# OSO-BOOK-C1-01.net
KiCad netlist of a schematic drawn in EAGLE
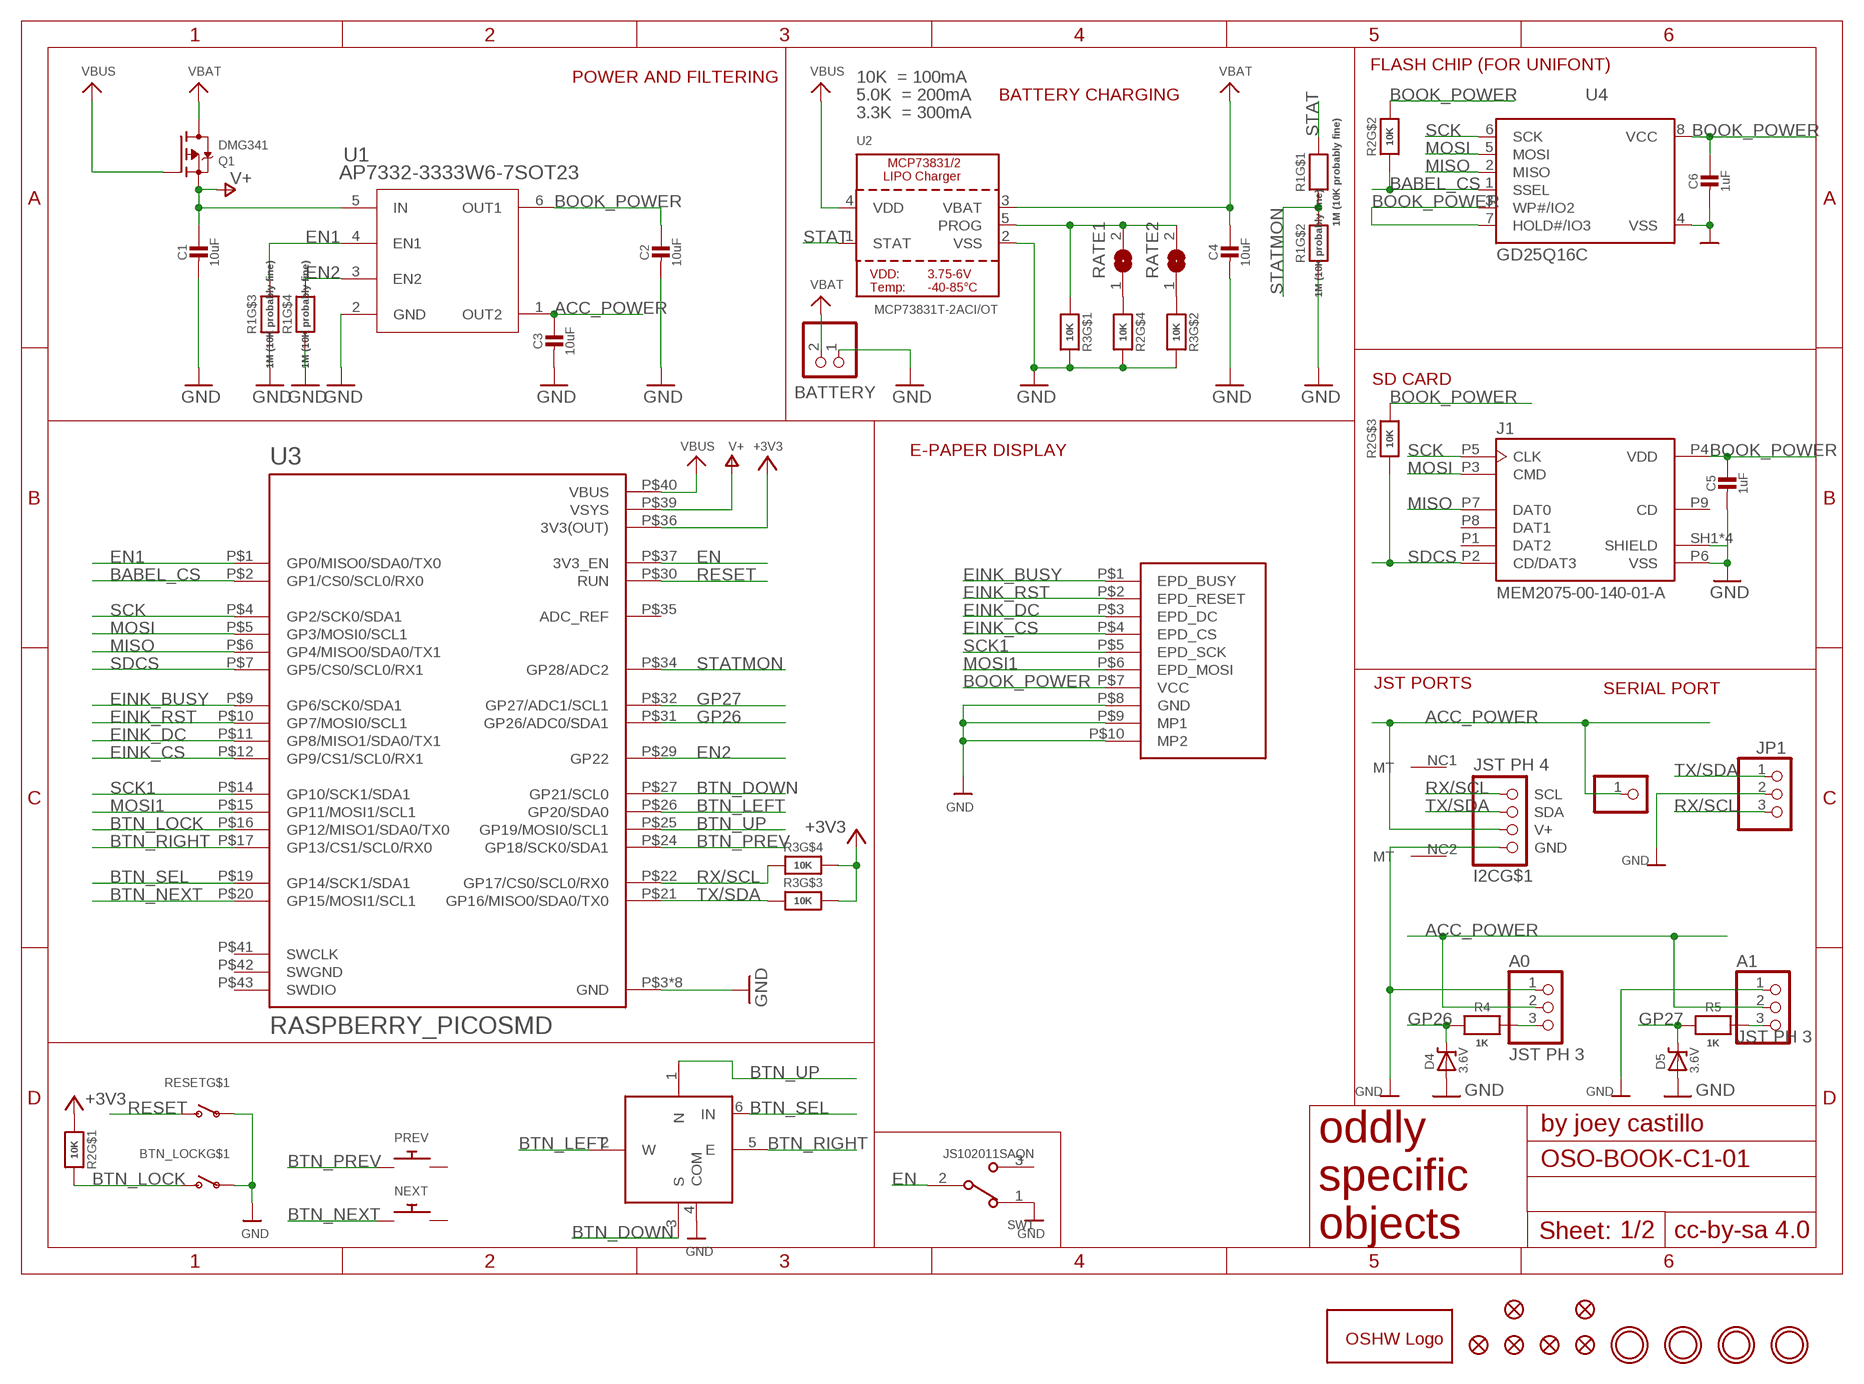
[diagram p0: schematic, sheet 1]
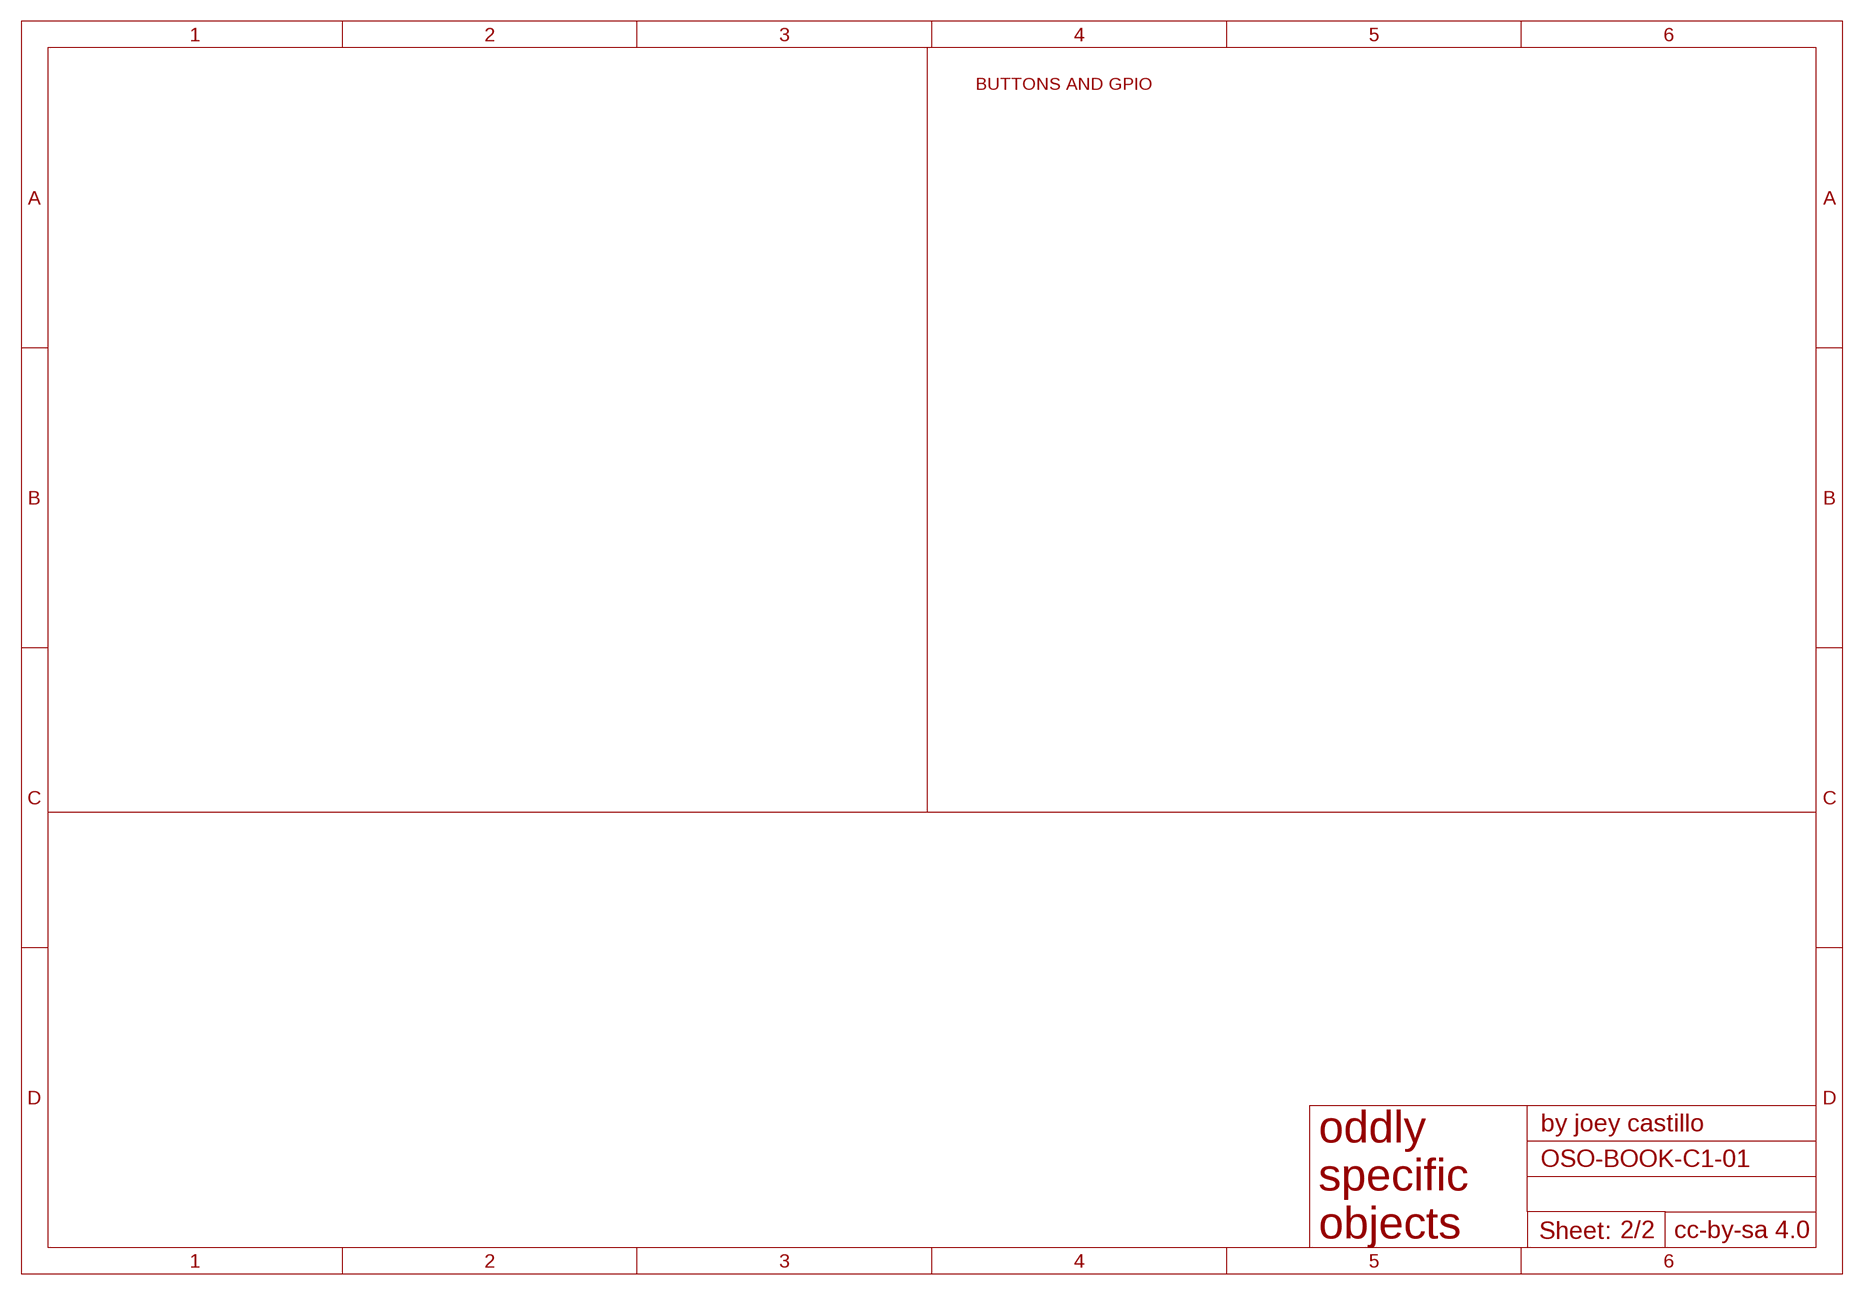
[diagram p1: schematic, sheet 2]

(export (version "E")
  (design (tool "Eeschema 10.0.6"))
  (components
    (comp (ref "A0")
      (value "JST PH 3")
      (footprint "eagle-import:JSTPH3")
      (libsource (lib "eagle-import") (part "CON_JST_PH_3PIN"))
    )
    (comp (ref "A1")
      (value "JST PH 3")
      (footprint "eagle-import:JSTPH3")
      (libsource (lib "eagle-import") (part "CON_JST_PH_3PIN"))
    )
    (comp (ref "BATTERY")
      (value "JSTPH")
      (footprint "eagle-import:JSTPH2")
      (libsource (lib "eagle-import") (part "CON_JST_PH_2PIN"))
    )
    (comp (ref "BTN_LOCK")
      (value "SWITCH_SPSTTL3330A")
      (footprint "eagle-import:TL3330A")
      (libsource (lib "eagle-import") (part "SWITCH_SPSTTL3330A"))
    )
    (comp (ref "C1")
      (value "10uF")
      (footprint "eagle-import:0805-NO")
      (libsource (lib "eagle-import") (part "CAP_CERAMIC0805-NOOUTLINE"))
    )
    (comp (ref "C2")
      (value "10uF")
      (footprint "eagle-import:0805-NO")
      (libsource (lib "eagle-import") (part "CAP_CERAMIC0805-NOOUTLINE"))
    )
    (comp (ref "C3")
      (value "10uF")
      (footprint "eagle-import:0805-NO")
      (libsource (lib "eagle-import") (part "CAP_CERAMIC0805-NOOUTLINE"))
    )
    (comp (ref "C4")
      (value "10uF")
      (footprint "eagle-import:0805-NO")
      (libsource (lib "eagle-import") (part "CAP_CERAMIC0805-NOOUTLINE"))
    )
    (comp (ref "C5")
      (value "1uF")
      (footprint "eagle-import:0805-NO")
      (libsource (lib "eagle-import") (part "CAP_CERAMIC0805-NOOUTLINE"))
    )
    (comp (ref "C6")
      (value "1uF")
      (footprint "eagle-import:0805-NO")
      (libsource (lib "eagle-import") (part "CAP_CERAMIC0805-NOOUTLINE"))
    )
    (comp (ref "D4")
      (value "3.6V")
      (footprint "eagle-import:SOD-123")
      (libsource (lib "eagle-import") (part "DIODE-ZENERSOD123"))
    )
    (comp (ref "D5")
      (value "3.6V")
      (footprint "eagle-import:SOD-123")
      (libsource (lib "eagle-import") (part "DIODE-ZENERSOD123"))
    )
    (comp (ref "FID1")
      (value "FIDUCIAL_1MM")
      (footprint "eagle-import:FIDUCIAL_1MM")
      (libsource (lib "eagle-import") (part "FIDUCIAL_1MM"))
    )
    (comp (ref "FID2")
      (value "FIDUCIAL_1MM")
      (footprint "eagle-import:FIDUCIAL_1MM")
      (libsource (lib "eagle-import") (part "FIDUCIAL_1MM"))
    )
    (comp (ref "FID3")
      (value "FIDUCIAL_1MM")
      (footprint "eagle-import:FIDUCIAL_1MM")
      (libsource (lib "eagle-import") (part "FIDUCIAL_1MM"))
    )
    (comp (ref "FID4")
      (value "FIDUCIAL_1MM")
      (footprint "eagle-import:FIDUCIAL_1MM")
      (libsource (lib "eagle-import") (part "FIDUCIAL_1MM"))
    )
    (comp (ref "FID5")
      (value "FIDUCIAL_1MM")
      (footprint "eagle-import:FIDUCIAL_1MM")
      (libsource (lib "eagle-import") (part "FIDUCIAL_1MM"))
    )
    (comp (ref "FID6")
      (value "FIDUCIAL_1MM")
      (footprint "eagle-import:FIDUCIAL_1MM")
      (libsource (lib "eagle-import") (part "FIDUCIAL_1MM"))
    )
    (comp (ref "GOLD_ORB_SM1")
      (value "OSHWLOGOLOGO5MM")
      (footprint "eagle-import:OSHW_5MM")
      (libsource (lib "eagle-import") (part "OSHWLOGOLOGO5MM"))
    )
    (comp (ref "I2C")
      (value "JST PH 4")
      (footprint "eagle-import:JSTPH4")
      (libsource (lib "eagle-import") (part "STEMMA_I2C_RASMT"))
    )
    (comp (ref "J1")
      (value "MEM2075-00-140-01-A")
      (footprint "eagle-import:GCT_MEM2075-00-140-01-A")
      (fields (field (name "MF") "Global Connector Technology"))
      (libsource (lib "eagle-import") (part "MEM2075-00-140-01-A"))
    )
    (comp (ref "JP1")
      (value "PINHD-1X3")
      (footprint "eagle-import:1X03")
      (libsource (lib "eagle-import") (part "PINHD-1X3"))
    )
    (comp (ref "JP2")
      (value "PINHD-1X1")
      (footprint "eagle-import:1X01")
      (libsource (lib "eagle-import") (part "PINHD-1X1"))
    )
    (comp (ref "NEXT")
      (value "SWITCH_PUSHBUTTON_3.5X6MM")
      (footprint "eagle-import:TACTILE_3X6MM")
      (libsource (lib "eagle-import") (part "SWITCH_PUSHBUTTON_3.5X6MM"))
    )
    (comp (ref "PREV")
      (value "SWITCH_PUSHBUTTON_3.5X6MM")
      (footprint "eagle-import:TACTILE_3X6MM")
      (libsource (lib "eagle-import") (part "SWITCH_PUSHBUTTON_3.5X6MM"))
    )
    (comp (ref "Q1")
      (value "DMG341")
      (footprint "eagle-import:SOT23-R")
      (libsource (lib "eagle-import") (part "MOSFET-P"))
    )
    (comp (ref "R1")
      (value "1M (10K probably fine)")
      (footprint "eagle-import:EXBV8V")
      (fields (field (name "MANUFACTURER_PART_NUMBER") "EXBV8V103JV"))
      (libsource (lib "eagle-import") (part "EXB-V8V103JV-GOOD"))
    )
    (comp (ref "R2")
      (value "10K")
      (footprint "eagle-import:EXBV8V")
      (fields (field (name "MANUFACTURER_PART_NUMBER") "EXBV8V103JV"))
      (libsource (lib "eagle-import") (part "EXB-V8V103JV-GOOD"))
    )
    (comp (ref "R3")
      (value "10K")
      (footprint "eagle-import:EXBV8V")
      (fields (field (name "MANUFACTURER_PART_NUMBER") "EXBV8V103JV"))
      (libsource (lib "eagle-import") (part "EXB-V8V103JV-GOOD"))
    )
    (comp (ref "R4")
      (value "1K")
      (footprint "eagle-import:0805-NO")
      (libsource (lib "eagle-import") (part "RESISTOR0805_NOOUTLINE"))
    )
    (comp (ref "R5")
      (value "1K")
      (footprint "eagle-import:0805-NO")
      (libsource (lib "eagle-import") (part "RESISTOR0805_NOOUTLINE"))
    )
    (comp (ref "RATE1")
      (value "SOLDERJUMPER")
      (footprint "eagle-import:SOLDERJUMPER_ARROW_NOPASTE")
      (libsource (lib "eagle-import") (part "SOLDERJUMPER"))
    )
    (comp (ref "RATE2")
      (value "SOLDERJUMPER")
      (footprint "eagle-import:SOLDERJUMPER_ARROW_NOPASTE")
      (libsource (lib "eagle-import") (part "SOLDERJUMPER"))
    )
    (comp (ref "RESET")
      (value "SWITCH_SPSTTL3330A")
      (footprint "eagle-import:TL3330A")
      (libsource (lib "eagle-import") (part "SWITCH_SPSTTL3330A"))
    )
    (comp (ref "SW1")
      (value "JS102011SAQN")
      (footprint "eagle-import:SW_JS102011SAQN")
      (fields (field (name "DIGI-KEY_PART_NUMBER") "401-1999-1-ND") (field (name "MF") "C&K"))
      (libsource (lib "eagle-import") (part "JS102011SAQN"))
    )
    (comp (ref "SW2")
      (value "NAVSWITCHSKQUABAUE010")
      (footprint "eagle-import:SKQUBAE010")
      (libsource (lib "eagle-import") (part "NAVSWITCHSKQUABAUE010"))
    )
    (comp (ref "U$1")
      (value "MOUNTINGHOLE2.5")
      (footprint "eagle-import:MOUNTINGHOLE_2.5_PLATED")
      (libsource (lib "eagle-import") (part "MOUNTINGHOLE2.5"))
    )
    (comp (ref "U$4")
      (value "MOUNTINGHOLE2.5")
      (footprint "eagle-import:MOUNTINGHOLE_2.5_PLATED")
      (libsource (lib "eagle-import") (part "MOUNTINGHOLE2.5"))
    )
    (comp (ref "U$5")
      (value "MOUNTINGHOLE2.5")
      (footprint "eagle-import:MOUNTINGHOLE_2.5_PLATED")
      (libsource (lib "eagle-import") (part "MOUNTINGHOLE2.5"))
    )
    (comp (ref "U$7")
      (value "MOUNTINGHOLE2.5")
      (footprint "eagle-import:MOUNTINGHOLE_2.5_PLATED")
      (libsource (lib "eagle-import") (part "MOUNTINGHOLE2.5"))
    )
    (comp (ref "U$11")
      (value "OSO-BOOK-C2-01")
      (footprint "eagle-import:OSO-BOOK-C2-01")
      (libsource (lib "eagle-import") (part "OSO-BOOK-C2-01"))
    )
    (comp (ref "U1")
      (value "AP7332-3333W6-7SOT23")
      (footprint "eagle-import:SOT23-6")
      (libsource (lib "eagle-import") (part "AP7332-3333W6-7SOT23"))
    )
    (comp (ref "U2")
      (value "MCP73831T-2ACI/OT")
      (footprint "eagle-import:SOT23-5")
      (libsource (lib "eagle-import") (part "MCP73831/2"))
    )
    (comp (ref "U3")
      (value "RASPBERRY_PICOSMD")
      (footprint "eagle-import:PICO-PKG-SMD")
      (libsource (lib "eagle-import") (part "RASPBERRY_PICOSMD"))
    )
    (comp (ref "U4")
      (value "GD25Q16C")
      (footprint "eagle-import:MICROBUILDER_SOIC8_150MIL")
      (libsource (lib "eagle-import") (part "MICROBUILDER_SPIFLASH_SOIC8"))
    )
  )
  (nets
    (net (code "1") (name "+3V3") (class "Default")
      (node (ref "R2") (pin "1") (pinfunction "1_1") (pintype "passive"))
      (node (ref "R3") (pin "5") (pinfunction "2_5") (pintype "passive"))
      (node (ref "R3") (pin "6") (pinfunction "2_6") (pintype "passive"))
      (node (ref "U3") (pin "P$36") (pinfunction "3V3(OUT)_P$36") (pintype "power_in"))
    )
    (net (code "2") (name "ACC_POWER") (class "Default")
      (node (ref "A0") (pin "2") (pinfunction "2_2") (pintype "passive"))
      (node (ref "A1") (pin "2") (pinfunction "2_2") (pintype "passive"))
      (node (ref "C3") (pin "1") (pinfunction "1_1") (pintype "passive"))
      (node (ref "I2C") (pin "2") (pinfunction "V+_2") (pintype "passive"))
      (node (ref "JP2") (pin "1") (pinfunction "1_1") (pintype "passive"))
      (node (ref "U1") (pin "1") (pinfunction "OUT2_1") (pintype "output"))
    )
    (net (code "3") (name "BABEL_CS") (class "Default")
      (node (ref "R2") (pin "2") (pinfunction "1_2") (pintype "passive"))
      (node (ref "U3") (pin "P$2") (pinfunction "GP1/CS0/SCL0/RX0_P$2") (pintype "bidirectional"))
      (node (ref "U4") (pin "1") (pinfunction "SSEL_1") (pintype "bidirectional"))
    )
    (net (code "4") (name "BOOK_POWER") (class "Default")
      (node (ref "C2") (pin "1") (pinfunction "1_1") (pintype "passive"))
      (node (ref "C5") (pin "1") (pinfunction "1_1") (pintype "passive"))
      (node (ref "C6") (pin "1") (pinfunction "1_1") (pintype "passive"))
      (node (ref "J1") (pin "P4") (pinfunction "VDD_P4") (pintype "power_in"))
      (node (ref "R2") (pin "6") (pinfunction "2_6") (pintype "passive"))
      (node (ref "R2") (pin "7") (pinfunction "2_7") (pintype "passive"))
      (node (ref "U$11") (pin "P$7") (pinfunction "VCC_P$7") (pintype "bidirectional"))
      (node (ref "U1") (pin "6") (pinfunction "OUT1_6") (pintype "output"))
      (node (ref "U4") (pin "3") (pinfunction "WP#/IO2_3") (pintype "bidirectional"))
      (node (ref "U4") (pin "7") (pinfunction "HOLD#/IO3_7") (pintype "bidirectional"))
      (node (ref "U4") (pin "8") (pinfunction "VCC_8") (pintype "bidirectional"))
    )
    (net (code "5") (name "BTN_DOWN") (class "Default")
      (node (ref "SW2") (pin "3") (pinfunction "S_3") (pintype "bidirectional"))
      (node (ref "U3") (pin "P$27") (pinfunction "GP21/SCL0_P$27") (pintype "bidirectional"))
    )
    (net (code "6") (name "BTN_LEFT") (class "Default")
      (node (ref "SW2") (pin "2") (pinfunction "W_2") (pintype "bidirectional"))
      (node (ref "U3") (pin "P$26") (pinfunction "GP20/SDA0_P$26") (pintype "bidirectional"))
    )
    (net (code "7") (name "BTN_LOCK") (class "Default")
      (node (ref "BTN_LOCK") (pin "P$2") (pinfunction "S_P$2") (pintype "passive"))
      (node (ref "R2") (pin "8") (pinfunction "2_8") (pintype "passive"))
      (node (ref "U3") (pin "P$16") (pinfunction "GP12/MISO1/SDA0/TX0_P$16") (pintype "bidirectional"))
    )
    (net (code "8") (name "BTN_NEXT") (class "Default")
      (node (ref "NEXT") (pin "P$1") (pinfunction "P$1_P$1") (pintype "passive"))
      (node (ref "U3") (pin "P$20") (pinfunction "GP15/MOSI1/SCL1_P$20") (pintype "bidirectional"))
    )
    (net (code "9") (name "BTN_PREV") (class "Default")
      (node (ref "PREV") (pin "P$1") (pinfunction "P$1_P$1") (pintype "passive"))
      (node (ref "U3") (pin "P$24") (pinfunction "GP18/SCK0/SDA1_P$24") (pintype "bidirectional"))
    )
    (net (code "10") (name "BTN_RIGHT") (class "Default")
      (node (ref "SW2") (pin "5") (pinfunction "E_5") (pintype "bidirectional"))
      (node (ref "U3") (pin "P$17") (pinfunction "GP13/CS1/SCL0/RX0_P$17") (pintype "bidirectional"))
    )
    (net (code "11") (name "BTN_SEL") (class "Default")
      (node (ref "SW2") (pin "6") (pinfunction "IN_6") (pintype "bidirectional"))
      (node (ref "U3") (pin "P$19") (pinfunction "GP14/SCK1/SDA1_P$19") (pintype "bidirectional"))
    )
    (net (code "12") (name "BTN_UP") (class "Default")
      (node (ref "SW2") (pin "1") (pinfunction "N_1") (pintype "bidirectional"))
      (node (ref "U3") (pin "P$25") (pinfunction "GP19/MOSI0/SCL1_P$25") (pintype "bidirectional"))
    )
    (net (code "13") (name "EINK_BUSY") (class "Default")
      (node (ref "U$11") (pin "P$1") (pinfunction "EPD_BUSY_P$1") (pintype "bidirectional"))
      (node (ref "U3") (pin "P$9") (pinfunction "GP6/SCK0/SDA1_P$9") (pintype "bidirectional"))
    )
    (net (code "14") (name "EINK_CS") (class "Default")
      (node (ref "U$11") (pin "P$4") (pinfunction "EPD_CS_P$4") (pintype "bidirectional"))
      (node (ref "U3") (pin "P$12") (pinfunction "GP9/CS1/SCL0/RX1_P$12") (pintype "bidirectional"))
    )
    (net (code "15") (name "EINK_DC") (class "Default")
      (node (ref "U$11") (pin "P$3") (pinfunction "EPD_DC_P$3") (pintype "bidirectional"))
      (node (ref "U3") (pin "P$11") (pinfunction "GP8/MISO1/SDA0/TX1_P$11") (pintype "bidirectional"))
    )
    (net (code "16") (name "EINK_RST") (class "Default")
      (node (ref "U$11") (pin "P$2") (pinfunction "EPD_RESET_P$2") (pintype "bidirectional"))
      (node (ref "U3") (pin "P$10") (pinfunction "GP7/MOSI0/SCL1_P$10") (pintype "bidirectional"))
    )
    (net (code "17") (name "EN") (class "Default")
      (node (ref "SW1") (pin "2") (pinfunction "2_2") (pintype "passive"))
      (node (ref "U3") (pin "P$37") (pinfunction "3V3_EN_P$37") (pintype "input"))
    )
    (net (code "18") (name "EN1") (class "Default")
      (node (ref "R1") (pin "3") (pinfunction "1_3") (pintype "passive"))
      (node (ref "U1") (pin "4") (pinfunction "EN1_4") (pintype "input"))
      (node (ref "U3") (pin "P$1") (pinfunction "GP0/MISO0/SDA0/TX0_P$1") (pintype "bidirectional"))
    )
    (net (code "19") (name "EN2") (class "Default")
      (node (ref "R1") (pin "4") (pinfunction "1_4") (pintype "passive"))
      (node (ref "U1") (pin "3") (pinfunction "EN2_3") (pintype "input"))
      (node (ref "U3") (pin "P$29") (pinfunction "GP22_P$29") (pintype "bidirectional"))
    )
    (net (code "20") (name "GND") (class "Default")
      (node (ref "A0") (pin "1") (pinfunction "1_1") (pintype "passive"))
      (node (ref "A1") (pin "1") (pinfunction "1_1") (pintype "passive"))
      (node (ref "BATTERY") (pin "1") (pinfunction "1_1") (pintype "passive"))
      (node (ref "BTN_LOCK") (pin "P$1") (pinfunction "P_P$1") (pintype "passive"))
      (node (ref "C1") (pin "2") (pinfunction "2_2") (pintype "passive"))
      (node (ref "C2") (pin "2") (pinfunction "2_2") (pintype "passive"))
      (node (ref "C3") (pin "2") (pinfunction "2_2") (pintype "passive"))
      (node (ref "C4") (pin "2") (pinfunction "2_2") (pintype "passive"))
      (node (ref "C5") (pin "2") (pinfunction "2_2") (pintype "passive"))
      (node (ref "C6") (pin "2") (pinfunction "2_2") (pintype "passive"))
      (node (ref "D4") (pin "A") (pinfunction "A_A") (pintype "passive"))
      (node (ref "D5") (pin "A") (pinfunction "A_A") (pintype "passive"))
      (node (ref "I2C") (pin "1") (pinfunction "GND_1") (pintype "passive"))
      (node (ref "J1") (pin "P6") (pinfunction "VSS_P6") (pintype "power_in"))
      (node (ref "J1") (pin "SH1") (pinfunction "SHIELD_SH1") (pintype "power_in"))
      (node (ref "J1") (pin "SH2") (pinfunction "SHIELD_SH2") (pintype "power_in"))
      (node (ref "J1") (pin "SH3") (pinfunction "SHIELD_SH3") (pintype "power_in"))
      (node (ref "J1") (pin "SH4") (pinfunction "SHIELD_SH4") (pintype "power_in"))
      (node (ref "JP1") (pin "2") (pinfunction "2_2") (pintype "passive"))
      (node (ref "R1") (pin "2") (pinfunction "1_2") (pintype "passive"))
      (node (ref "R1") (pin "5") (pinfunction "2_5") (pintype "passive"))
      (node (ref "R1") (pin "6") (pinfunction "2_6") (pintype "passive"))
      (node (ref "R2") (pin "5") (pinfunction "2_5") (pintype "passive"))
      (node (ref "R3") (pin "7") (pinfunction "2_7") (pintype "passive"))
      (node (ref "R3") (pin "8") (pinfunction "2_8") (pintype "passive"))
      (node (ref "RESET") (pin "P$1") (pinfunction "P_P$1") (pintype "passive"))
      (node (ref "SW1") (pin "1") (pinfunction "1_1") (pintype "passive"))
      (node (ref "SW2") (pin "4") (pinfunction "COM_4") (pintype "bidirectional"))
      (node (ref "U$11") (pin "P$10") (pinfunction "MP2_P$10") (pintype "bidirectional"))
      (node (ref "U$11") (pin "P$8") (pinfunction "GND_P$8") (pintype "bidirectional"))
      (node (ref "U$11") (pin "P$9") (pinfunction "MP1_P$9") (pintype "bidirectional"))
      (node (ref "U1") (pin "2") (pinfunction "GND_2") (pintype "power_in"))
      (node (ref "U2") (pin "2") (pinfunction "VSS_2") (pintype "power_in"))
      (node (ref "U3") (pin "P$13") (pinfunction "GND_P$13") (pintype "power_in"))
      (node (ref "U3") (pin "P$18") (pinfunction "GND_P$18") (pintype "power_in"))
      (node (ref "U3") (pin "P$23") (pinfunction "GND_P$23") (pintype "power_in"))
      (node (ref "U3") (pin "P$28") (pinfunction "GND_P$28") (pintype "power_in"))
      (node (ref "U3") (pin "P$3") (pinfunction "GND_P$3") (pintype "power_in"))
      (node (ref "U3") (pin "P$33") (pinfunction "GND_P$33") (pintype "power_in"))
      (node (ref "U3") (pin "P$38") (pinfunction "GND_P$38") (pintype "power_in"))
      (node (ref "U3") (pin "P$8") (pinfunction "GND_P$8") (pintype "power_in"))
      (node (ref "U4") (pin "4") (pinfunction "VSS_4") (pintype "bidirectional"))
    )
    (net (code "21") (name "GP26") (class "Default")
      (node (ref "D4") (pin "C") (pinfunction "C_C") (pintype "passive"))
      (node (ref "R4") (pin "2") (pinfunction "2_2") (pintype "passive"))
      (node (ref "U3") (pin "P$31") (pinfunction "GP26/ADC0/SDA1_P$31") (pintype "bidirectional"))
    )
    (net (code "22") (name "GP27") (class "Default")
      (node (ref "D5") (pin "C") (pinfunction "C_C") (pintype "passive"))
      (node (ref "R5") (pin "2") (pinfunction "2_2") (pintype "passive"))
      (node (ref "U3") (pin "P$32") (pinfunction "GP27/ADC1/SCL1_P$32") (pintype "bidirectional"))
    )
    (net (code "23") (name "MISO") (class "Default")
      (node (ref "J1") (pin "P7") (pinfunction "DAT0_P7") (pintype "bidirectional"))
      (node (ref "U3") (pin "P$6") (pinfunction "GP4/MISO0/SDA0/TX1_P$6") (pintype "bidirectional"))
      (node (ref "U4") (pin "2") (pinfunction "MISO_2") (pintype "bidirectional"))
    )
    (net (code "24") (name "MOSI") (class "Default")
      (node (ref "J1") (pin "P3") (pinfunction "CMD_P3") (pintype "bidirectional"))
      (node (ref "U3") (pin "P$5") (pinfunction "GP3/MOSI0/SCL1_P$5") (pintype "bidirectional"))
      (node (ref "U4") (pin "5") (pinfunction "MOSI_5") (pintype "bidirectional"))
    )
    (net (code "25") (name "MOSI1") (class "Default")
      (node (ref "U$11") (pin "P$6") (pinfunction "EPD_MOSI_P$6") (pintype "bidirectional"))
      (node (ref "U3") (pin "P$15") (pinfunction "GP11/MOSI1/SCL1_P$15") (pintype "bidirectional"))
    )
    (net (code "26") (name "Net-(A0-Pad3)") (class "Default")
      (node (ref "A0") (pin "3") (pinfunction "3_3") (pintype "passive"))
      (node (ref "R4") (pin "1") (pinfunction "1_1") (pintype "passive"))
    )
    (net (code "27") (name "Net-(A1-Pad3)") (class "Default")
      (node (ref "A1") (pin "3") (pinfunction "3_3") (pintype "passive"))
      (node (ref "R5") (pin "1") (pinfunction "1_1") (pintype "passive"))
    )
    (net (code "28") (name "Net-(R2D-1)") (class "Default")
      (node (ref "R2") (pin "4") (pinfunction "1_4") (pintype "passive"))
      (node (ref "RATE1") (pin "1") (pinfunction "1_1") (pintype "passive"))
    )
    (net (code "29") (name "Net-(R3B-1)") (class "Default")
      (node (ref "R3") (pin "2") (pinfunction "1_2") (pintype "passive"))
      (node (ref "RATE2") (pin "1") (pinfunction "1_1") (pintype "passive"))
    )
    (net (code "30") (name "Net-(U2-PROG)") (class "Default")
      (node (ref "R3") (pin "1") (pinfunction "1_1") (pintype "passive"))
      (node (ref "RATE1") (pin "2") (pinfunction "2_2") (pintype "passive"))
      (node (ref "RATE2") (pin "2") (pinfunction "2_2") (pintype "passive"))
      (node (ref "U2") (pin "5") (pinfunction "PROG_5") (pintype "input"))
    )
    (net (code "31") (name "RESET") (class "Default")
      (node (ref "RESET") (pin "P$2") (pinfunction "S_P$2") (pintype "passive"))
      (node (ref "U3") (pin "P$30") (pinfunction "RUN_P$30") (pintype "input"))
    )
    (net (code "32") (name "RX{slash}SCL") (class "Default")
      (node (ref "I2C") (pin "4") (pinfunction "SCL_4") (pintype "passive"))
      (node (ref "JP1") (pin "3") (pinfunction "3_3") (pintype "passive"))
      (node (ref "R3") (pin "4") (pinfunction "1_4") (pintype "passive"))
      (node (ref "U3") (pin "P$22") (pinfunction "GP17/CS0/SCL0/RX0_P$22") (pintype "bidirectional"))
    )
    (net (code "33") (name "SCK") (class "Default")
      (node (ref "J1") (pin "P5") (pinfunction "CLK_P5") (pintype "bidirectional"))
      (node (ref "U3") (pin "P$4") (pinfunction "GP2/SCK0/SDA1_P$4") (pintype "bidirectional"))
      (node (ref "U4") (pin "6") (pinfunction "SCK_6") (pintype "bidirectional"))
    )
    (net (code "34") (name "SCK1") (class "Default")
      (node (ref "U$11") (pin "P$5") (pinfunction "EPD_SCK_P$5") (pintype "bidirectional"))
      (node (ref "U3") (pin "P$14") (pinfunction "GP10/SCK1/SDA1_P$14") (pintype "bidirectional"))
    )
    (net (code "35") (name "SDCS") (class "Default")
      (node (ref "J1") (pin "P2") (pinfunction "CD/DAT3_P2") (pintype "bidirectional"))
      (node (ref "R2") (pin "3") (pinfunction "1_3") (pintype "passive"))
      (node (ref "U3") (pin "P$7") (pinfunction "GP5/CS0/SCL0/RX1_P$7") (pintype "bidirectional"))
    )
    (net (code "36") (name "STAT") (class "Default")
      (node (ref "R1") (pin "8") (pinfunction "2_8") (pintype "passive"))
      (node (ref "U2") (pin "1") (pinfunction "STAT_1") (pintype "output"))
    )
    (net (code "37") (name "STATMON") (class "Default")
      (node (ref "R1") (pin "1") (pinfunction "1_1") (pintype "passive"))
      (node (ref "R1") (pin "7") (pinfunction "2_7") (pintype "passive"))
      (node (ref "U3") (pin "P$34") (pinfunction "GP28/ADC2_P$34") (pintype "bidirectional"))
    )
    (net (code "38") (name "SWGND") (class "Default")
      (node (ref "U3") (pin "P$42") (pinfunction "SWGND_P$42") (pintype "power_in"))
    )
    (net (code "39") (name "TX{slash}SDA") (class "Default")
      (node (ref "I2C") (pin "3") (pinfunction "SDA_3") (pintype "passive"))
      (node (ref "JP1") (pin "1") (pinfunction "1_1") (pintype "passive"))
      (node (ref "R3") (pin "3") (pinfunction "1_3") (pintype "passive"))
      (node (ref "U3") (pin "P$21") (pinfunction "GP16/MISO0/SDA0/TX0_P$21") (pintype "bidirectional"))
    )
    (net (code "40") (name "V+") (class "Default")
      (node (ref "C1") (pin "1") (pinfunction "1_1") (pintype "passive"))
      (node (ref "Q1") (pin "2") (pinfunction "S_2") (pintype "passive"))
      (node (ref "U1") (pin "5") (pinfunction "IN_5") (pintype "input"))
      (node (ref "U3") (pin "P$39") (pinfunction "VSYS_P$39") (pintype "power_in"))
    )
    (net (code "41") (name "VBAT") (class "Default")
      (node (ref "BATTERY") (pin "2") (pinfunction "2_2") (pintype "passive"))
      (node (ref "C4") (pin "1") (pinfunction "1_1") (pintype "passive"))
      (node (ref "Q1") (pin "3") (pinfunction "D_3") (pintype "passive"))
      (node (ref "U2") (pin "3") (pinfunction "VBAT_3") (pintype "power_in"))
    )
    (net (code "42") (name "VBUS") (class "Default")
      (node (ref "Q1") (pin "1") (pinfunction "G_1") (pintype "passive"))
      (node (ref "U2") (pin "4") (pinfunction "VDD_4") (pintype "power_in"))
      (node (ref "U3") (pin "P$40") (pinfunction "VBUS_P$40") (pintype "power_in"))
    )
    (net (code "43") (name "unconnected-(I2CB-MT-PadNC1)") (class "Default")
      (node (ref "I2C") (pin "NC1") (pinfunction "MT_NC1") (pintype "bidirectional"))
    )
    (net (code "44") (name "unconnected-(I2CC-MT-PadNC2)") (class "Default")
      (node (ref "I2C") (pin "NC2") (pinfunction "MT_NC2") (pintype "bidirectional"))
    )
    (net (code "45") (name "unconnected-(J1-CD-PadP9)") (class "Default")
      (node (ref "J1") (pin "P9") (pinfunction "CD_P9") (pintype "passive"))
    )
    (net (code "46") (name "unconnected-(J1-DAT1-PadP8)") (class "Default")
      (node (ref "J1") (pin "P8") (pinfunction "DAT1_P8") (pintype "bidirectional"))
    )
    (net (code "47") (name "unconnected-(J1-DAT2-PadP1)") (class "Default")
      (node (ref "J1") (pin "P1") (pinfunction "DAT2_P1") (pintype "bidirectional"))
    )
    (net (code "48") (name "unconnected-(NEXT-PadP$2)") (class "Default")
      (node (ref "NEXT") (pin "P$2") (pinfunction "P$2_P$2") (pintype "passive"))
    )
    (net (code "49") (name "unconnected-(PREV-PadP$2)") (class "Default")
      (node (ref "PREV") (pin "P$2") (pinfunction "P$2_P$2") (pintype "passive"))
    )
    (net (code "50") (name "unconnected-(SW1-Pad3)") (class "Default")
      (node (ref "SW1") (pin "3") (pinfunction "3_3") (pintype "passive"))
    )
    (net (code "51") (name "unconnected-(U3-ADC_REF-PadP$35)") (class "Default")
      (node (ref "U3") (pin "P$35") (pinfunction "ADC_REF_P$35") (pintype "input"))
    )
    (net (code "52") (name "unconnected-(U3-SWCLK-PadP$41)") (class "Default")
      (node (ref "U3") (pin "P$41") (pinfunction "SWCLK_P$41") (pintype "input"))
    )
    (net (code "53") (name "unconnected-(U3-SWDIO-PadP$43)") (class "Default")
      (node (ref "U3") (pin "P$43") (pinfunction "SWDIO_P$43") (pintype "bidirectional"))
    )
  )
)
